# HendiRemoteInterface_v010.net
KiCad netlist of a schematic drawn in EAGLE
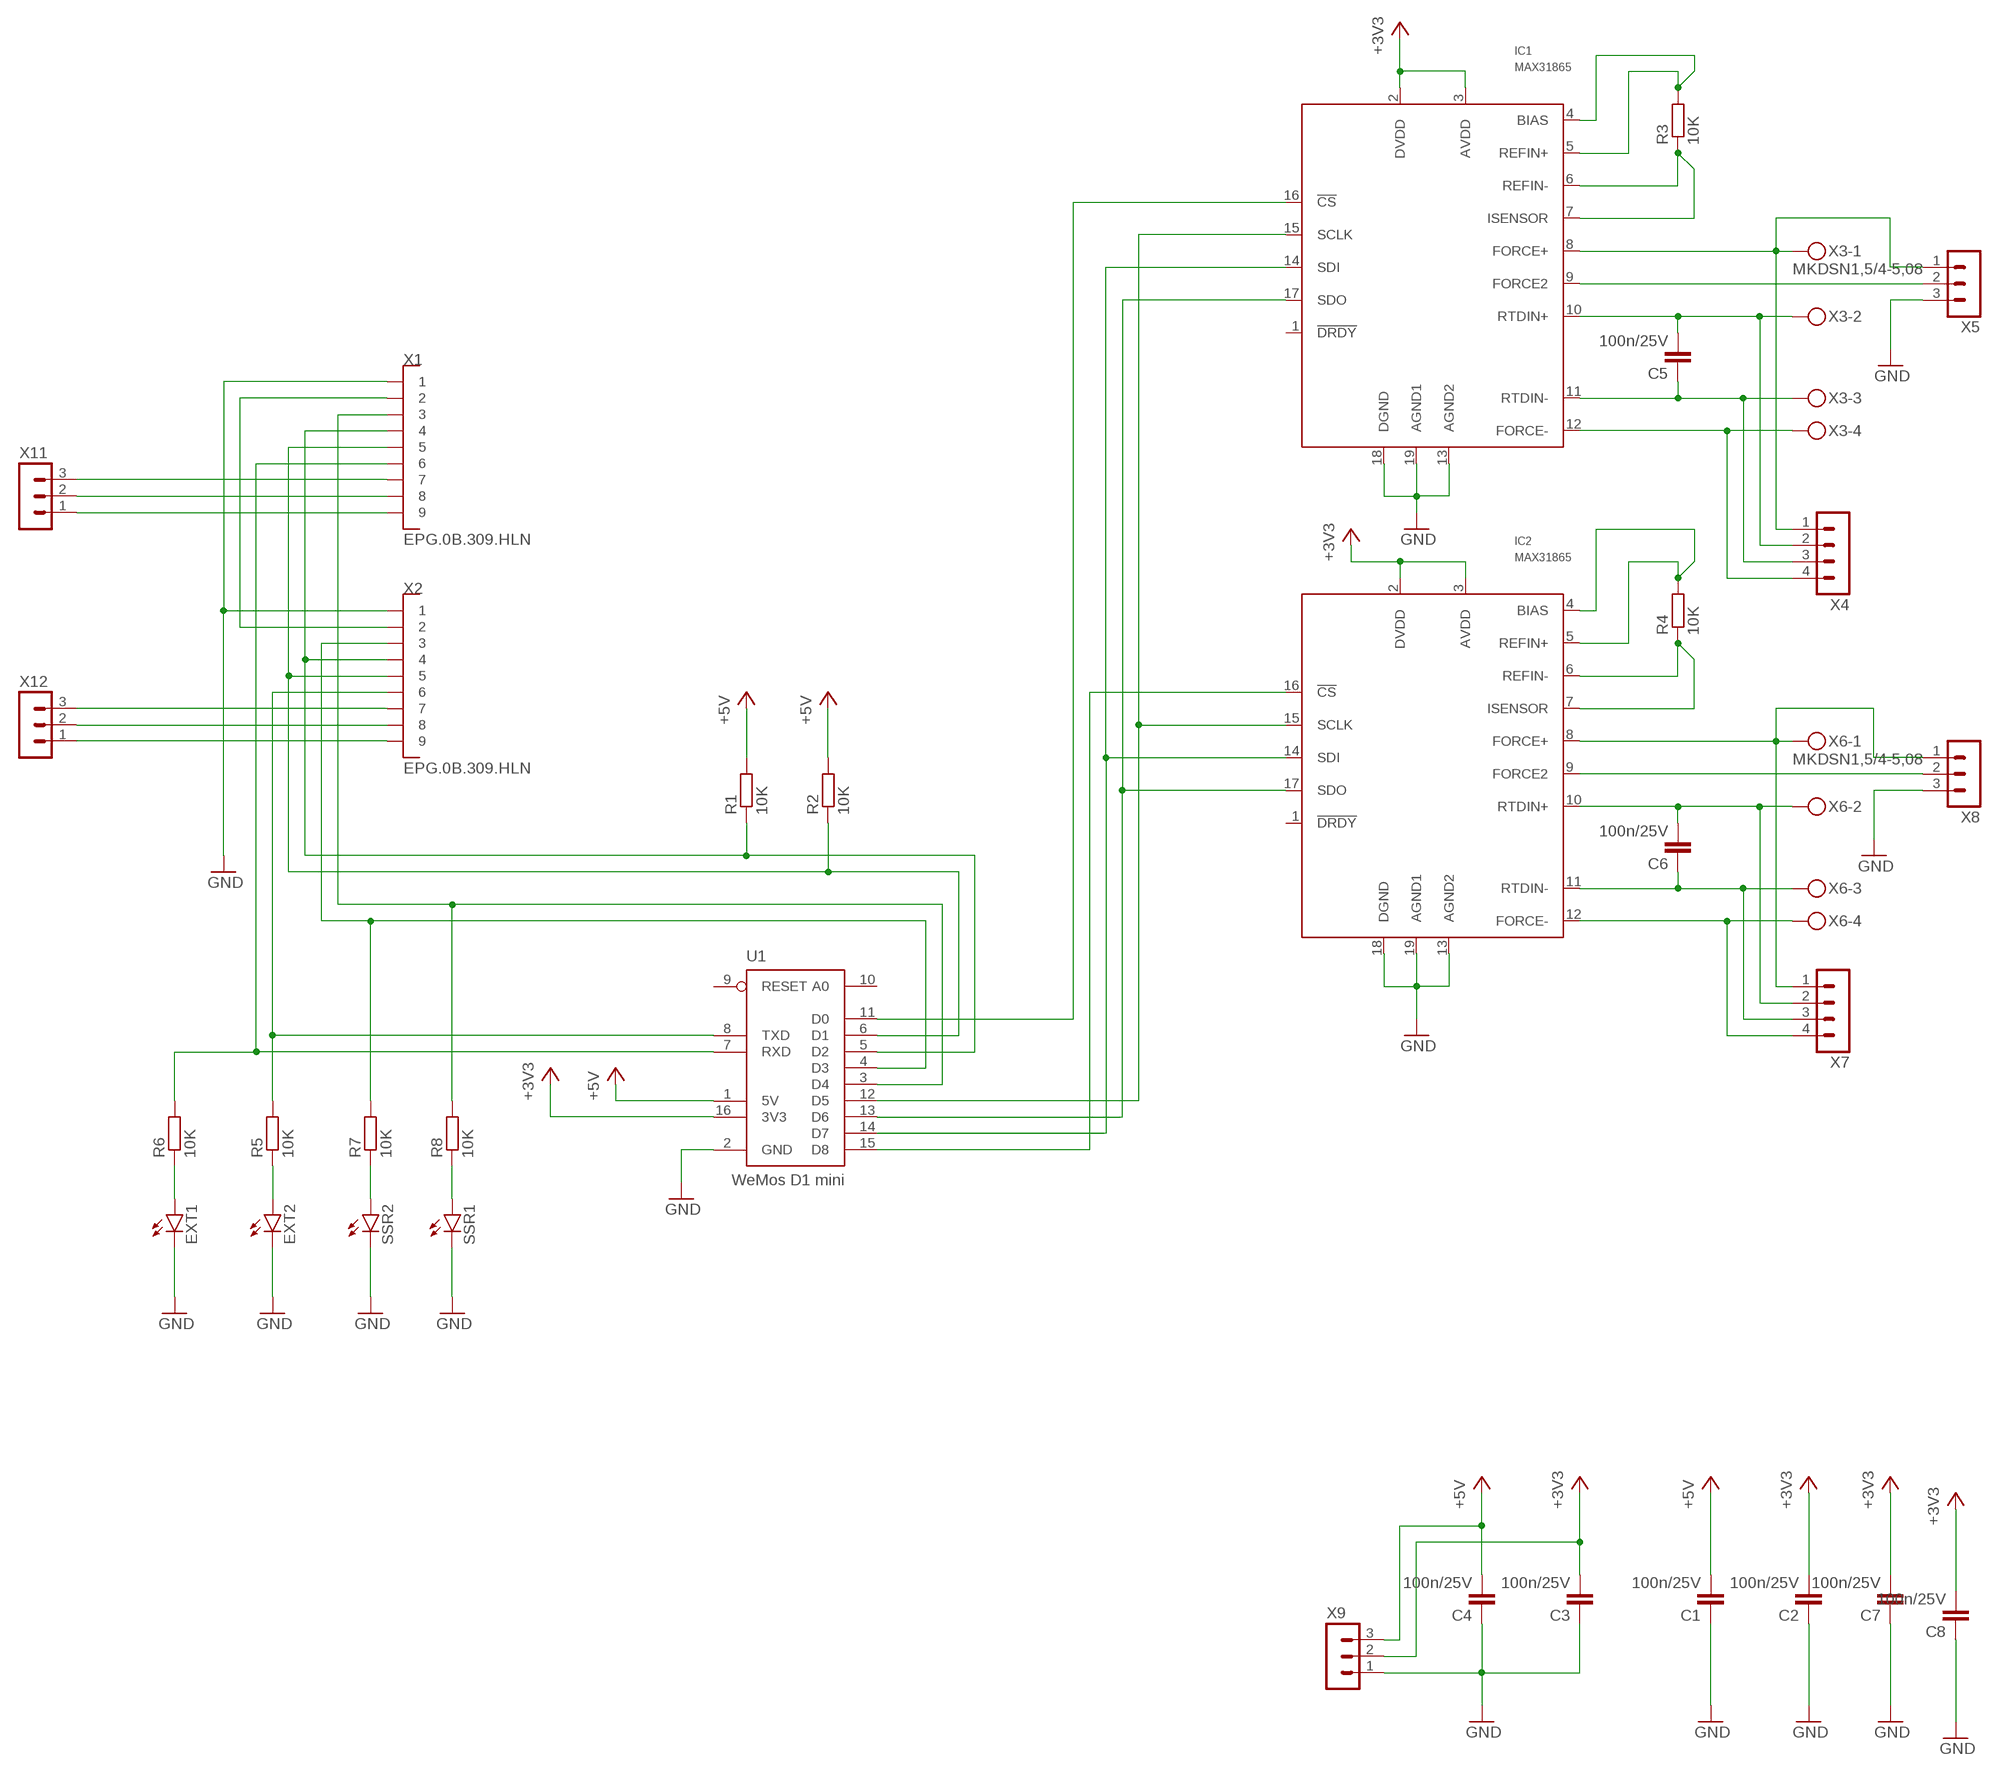
[diagram p0: schematic, sheet 1]

(export (version "E")
  (design (tool "Eeschema 10.0.6"))
  (components
    (comp (ref "C1")
      (value "100n/25V")
      (footprint "eagle-import:C0805")
      (libsource (lib "eagle-import") (part "C-EUC0805"))
    )
    (comp (ref "C2")
      (value "100n/25V")
      (footprint "eagle-import:C0805")
      (libsource (lib "eagle-import") (part "C-EUC0805"))
    )
    (comp (ref "C3")
      (value "100n/25V")
      (footprint "eagle-import:C0805")
      (libsource (lib "eagle-import") (part "C-EUC0805"))
    )
    (comp (ref "C4")
      (value "100n/25V")
      (footprint "eagle-import:C0805")
      (libsource (lib "eagle-import") (part "C-EUC0805"))
    )
    (comp (ref "C5")
      (value "100n/25V")
      (footprint "eagle-import:C0805")
      (libsource (lib "eagle-import") (part "C-EUC0805"))
    )
    (comp (ref "C6")
      (value "100n/25V")
      (footprint "eagle-import:C0805")
      (libsource (lib "eagle-import") (part "C-EUC0805"))
    )
    (comp (ref "C7")
      (value "100n/25V")
      (footprint "eagle-import:C0805")
      (libsource (lib "eagle-import") (part "C-EUC0805"))
    )
    (comp (ref "C8")
      (value "100n/25V")
      (footprint "eagle-import:C0805")
      (libsource (lib "eagle-import") (part "C-EUC0805"))
    )
    (comp (ref "EXT1")
      (value "LEDCHIP-LED0805")
      (footprint "eagle-import:CHIP-LED0805")
      (libsource (lib "eagle-import") (part "LEDCHIP-LED0805"))
    )
    (comp (ref "EXT2")
      (value "LEDCHIP-LED0805")
      (footprint "eagle-import:CHIP-LED0805")
      (libsource (lib "eagle-import") (part "LEDCHIP-LED0805"))
    )
    (comp (ref "IC1")
      (value "MAX31865")
      (footprint "eagle-import:SSOP20")
      (libsource (lib "eagle-import") (part "MAX31865-SSOPSSOP"))
    )
    (comp (ref "IC2")
      (value "MAX31865")
      (footprint "eagle-import:SSOP20")
      (libsource (lib "eagle-import") (part "MAX31865-SSOPSSOP"))
    )
    (comp (ref "R1")
      (value "10K")
      (footprint "eagle-import:R0805")
      (libsource (lib "eagle-import") (part "R-EU_R0805"))
    )
    (comp (ref "R2")
      (value "10K")
      (footprint "eagle-import:R0805")
      (libsource (lib "eagle-import") (part "R-EU_R0805"))
    )
    (comp (ref "R3")
      (value "10K")
      (footprint "eagle-import:R0805")
      (libsource (lib "eagle-import") (part "R-EU_R0805"))
    )
    (comp (ref "R4")
      (value "10K")
      (footprint "eagle-import:R0805")
      (libsource (lib "eagle-import") (part "R-EU_R0805"))
    )
    (comp (ref "R5")
      (value "10K")
      (footprint "eagle-import:R0805")
      (libsource (lib "eagle-import") (part "R-EU_R0805"))
    )
    (comp (ref "R6")
      (value "10K")
      (footprint "eagle-import:R0805")
      (libsource (lib "eagle-import") (part "R-EU_R0805"))
    )
    (comp (ref "R7")
      (value "10K")
      (footprint "eagle-import:R0805")
      (libsource (lib "eagle-import") (part "R-EU_R0805"))
    )
    (comp (ref "R8")
      (value "10K")
      (footprint "eagle-import:R0805")
      (libsource (lib "eagle-import") (part "R-EU_R0805"))
    )
    (comp (ref "SSR1")
      (value "LEDCHIP-LED0805")
      (footprint "eagle-import:CHIP-LED0805")
      (libsource (lib "eagle-import") (part "LEDCHIP-LED0805"))
    )
    (comp (ref "SSR2")
      (value "LEDCHIP-LED0805")
      (footprint "eagle-import:CHIP-LED0805")
      (libsource (lib "eagle-import") (part "LEDCHIP-LED0805"))
    )
    (comp (ref "U1")
      (value "WeMos D1 mini")
      (footprint "eagle-import:D1_MINI")
      (libsource (lib "eagle-import") (part "D1_MINI"))
    )
    (comp (ref "X1")
      (value "EPG.0B.309.HLN")
      (footprint "eagle-import:P19-EPG-EXG-0B.309")
      (libsource (lib "eagle-import") (part "EPG.0B.309.HLN"))
    )
    (comp (ref "X2")
      (value "EPG.0B.309.HLN")
      (footprint "eagle-import:P19-EPG-EXG-0B.309")
      (libsource (lib "eagle-import") (part "EPG.0B.309.HLN"))
    )
    (comp (ref "X3")
      (value "MKDSN1,5/4-5,08")
      (footprint "eagle-import:MKDSN1,5_4-5,08")
      (libsource (lib "eagle-import") (part "MKDSN1,5/4-5,08"))
    )
    (comp (ref "X4")
      (value "MA04-1")
      (footprint "eagle-import:MA04-1")
      (libsource (lib "eagle-import") (part "MA04-1"))
    )
    (comp (ref "X5")
      (value "MA03-1")
      (footprint "eagle-import:MA03-1")
      (libsource (lib "eagle-import") (part "MA03-1"))
    )
    (comp (ref "X6")
      (value "MKDSN1,5/4-5,08")
      (footprint "eagle-import:MKDSN1,5_4-5,08")
      (libsource (lib "eagle-import") (part "MKDSN1,5/4-5,08"))
    )
    (comp (ref "X7")
      (value "MA04-1")
      (footprint "eagle-import:MA04-1")
      (libsource (lib "eagle-import") (part "MA04-1"))
    )
    (comp (ref "X8")
      (value "MA03-1")
      (footprint "eagle-import:MA03-1")
      (libsource (lib "eagle-import") (part "MA03-1"))
    )
    (comp (ref "X9")
      (value "MA03-1")
      (footprint "eagle-import:MA03-1")
      (libsource (lib "eagle-import") (part "MA03-1"))
    )
    (comp (ref "X11")
      (value "MA03-1")
      (footprint "eagle-import:MA03-1")
      (libsource (lib "eagle-import") (part "MA03-1"))
    )
    (comp (ref "X12")
      (value "MA03-1")
      (footprint "eagle-import:MA03-1")
      (libsource (lib "eagle-import") (part "MA03-1"))
    )
  )
  (nets
    (net (code "1") (name "+3V3") (class "Default")
      (node (ref "C2") (pin "2") (pinfunction "2_2") (pintype "passive"))
      (node (ref "C3") (pin "2") (pinfunction "2_2") (pintype "passive"))
      (node (ref "C7") (pin "2") (pinfunction "2_2") (pintype "passive"))
      (node (ref "C8") (pin "2") (pinfunction "2_2") (pintype "passive"))
      (node (ref "IC1") (pin "2") (pinfunction "DVDD_2") (pintype "passive"))
      (node (ref "IC1") (pin "3") (pinfunction "AVDD_3") (pintype "passive"))
      (node (ref "IC2") (pin "2") (pinfunction "DVDD_2") (pintype "passive"))
      (node (ref "IC2") (pin "3") (pinfunction "AVDD_3") (pintype "passive"))
      (node (ref "U1") (pin "16") (pinfunction "3V3_16") (pintype "bidirectional"))
      (node (ref "X9") (pin "2") (pinfunction "2_2") (pintype "passive"))
    )
    (net (code "2") (name "+5V") (class "Default")
      (node (ref "C1") (pin "2") (pinfunction "2_2") (pintype "passive"))
      (node (ref "C4") (pin "2") (pinfunction "2_2") (pintype "passive"))
      (node (ref "R1") (pin "2") (pinfunction "2_2") (pintype "passive"))
      (node (ref "R2") (pin "2") (pinfunction "2_2") (pintype "passive"))
      (node (ref "U1") (pin "1") (pinfunction "5V_1") (pintype "bidirectional"))
      (node (ref "X9") (pin "3") (pinfunction "3_3") (pintype "passive"))
    )
    (net (code "3") (name "GND") (class "Default")
      (node (ref "C1") (pin "1") (pinfunction "1_1") (pintype "passive"))
      (node (ref "C2") (pin "1") (pinfunction "1_1") (pintype "passive"))
      (node (ref "C3") (pin "1") (pinfunction "1_1") (pintype "passive"))
      (node (ref "C4") (pin "1") (pinfunction "1_1") (pintype "passive"))
      (node (ref "C7") (pin "1") (pinfunction "1_1") (pintype "passive"))
      (node (ref "C8") (pin "1") (pinfunction "1_1") (pintype "passive"))
      (node (ref "EXT1") (pin "C") (pinfunction "C_C") (pintype "passive"))
      (node (ref "EXT2") (pin "C") (pinfunction "C_C") (pintype "passive"))
      (node (ref "IC1") (pin "13") (pinfunction "AGND2_13") (pintype "passive"))
      (node (ref "IC1") (pin "18") (pinfunction "DGND_18") (pintype "passive"))
      (node (ref "IC1") (pin "19") (pinfunction "AGND1_19") (pintype "passive"))
      (node (ref "IC2") (pin "13") (pinfunction "AGND2_13") (pintype "passive"))
      (node (ref "IC2") (pin "18") (pinfunction "DGND_18") (pintype "passive"))
      (node (ref "IC2") (pin "19") (pinfunction "AGND1_19") (pintype "passive"))
      (node (ref "SSR1") (pin "C") (pinfunction "C_C") (pintype "passive"))
      (node (ref "SSR2") (pin "C") (pinfunction "C_C") (pintype "passive"))
      (node (ref "U1") (pin "2") (pinfunction "GND_2") (pintype "bidirectional"))
      (node (ref "X1") (pin "1") (pinfunction "1_1") (pintype "bidirectional"))
      (node (ref "X2") (pin "1") (pinfunction "1_1") (pintype "bidirectional"))
      (node (ref "X5") (pin "3") (pinfunction "3_3") (pintype "passive"))
      (node (ref "X8") (pin "3") (pinfunction "3_3") (pintype "passive"))
      (node (ref "X9") (pin "1") (pinfunction "1_1") (pintype "passive"))
    )
    (net (code "4") (name "Net-(EXT1-PadA)") (class "Default")
      (node (ref "EXT1") (pin "A") (pinfunction "A_A") (pintype "passive"))
      (node (ref "R6") (pin "1") (pinfunction "1_1") (pintype "passive"))
    )
    (net (code "5") (name "Net-(EXT2-PadA)") (class "Default")
      (node (ref "EXT2") (pin "A") (pinfunction "A_A") (pintype "passive"))
      (node (ref "R5") (pin "1") (pinfunction "1_1") (pintype "passive"))
    )
    (net (code "6") (name "Net-(IC1-BIAS)") (class "Default")
      (node (ref "IC1") (pin "4") (pinfunction "BIAS_4") (pintype "passive"))
      (node (ref "IC1") (pin "5") (pinfunction "REFIN+_5") (pintype "passive"))
      (node (ref "R3") (pin "2") (pinfunction "2_2") (pintype "passive"))
    )
    (net (code "7") (name "Net-(IC1-FORCE+)") (class "Default")
      (node (ref "IC1") (pin "8") (pinfunction "FORCE+_8") (pintype "passive"))
      (node (ref "X3") (pin "1") (pinfunction "KL_1") (pintype "passive"))
      (node (ref "X4") (pin "1") (pinfunction "1_1") (pintype "passive"))
      (node (ref "X5") (pin "1") (pinfunction "1_1") (pintype "passive"))
    )
    (net (code "8") (name "Net-(IC1-FORCE-)") (class "Default")
      (node (ref "IC1") (pin "12") (pinfunction "FORCE-_12") (pintype "passive"))
      (node (ref "X3") (pin "4") (pinfunction "KL_4") (pintype "passive"))
      (node (ref "X4") (pin "4") (pinfunction "4_4") (pintype "passive"))
    )
    (net (code "9") (name "Net-(IC1-FORCE2)") (class "Default")
      (node (ref "IC1") (pin "9") (pinfunction "FORCE2_9") (pintype "passive"))
      (node (ref "X5") (pin "2") (pinfunction "2_2") (pintype "passive"))
    )
    (net (code "10") (name "Net-(IC1-ISENSOR)") (class "Default")
      (node (ref "IC1") (pin "6") (pinfunction "REFIN-_6") (pintype "passive"))
      (node (ref "IC1") (pin "7") (pinfunction "ISENSOR_7") (pintype "passive"))
      (node (ref "R3") (pin "1") (pinfunction "1_1") (pintype "passive"))
    )
    (net (code "11") (name "Net-(IC1-RTDIN+)") (class "Default")
      (node (ref "C5") (pin "2") (pinfunction "2_2") (pintype "passive"))
      (node (ref "IC1") (pin "10") (pinfunction "RTDIN+_10") (pintype "passive"))
      (node (ref "X3") (pin "2") (pinfunction "KL_2") (pintype "passive"))
      (node (ref "X4") (pin "2") (pinfunction "2_2") (pintype "passive"))
    )
    (net (code "12") (name "Net-(IC1-RTDIN-)") (class "Default")
      (node (ref "C5") (pin "1") (pinfunction "1_1") (pintype "passive"))
      (node (ref "IC1") (pin "11") (pinfunction "RTDIN-_11") (pintype "passive"))
      (node (ref "X3") (pin "3") (pinfunction "KL_3") (pintype "passive"))
      (node (ref "X4") (pin "3") (pinfunction "3_3") (pintype "passive"))
    )
    (net (code "13") (name "Net-(IC1-SCLK)") (class "Default")
      (node (ref "IC1") (pin "15") (pinfunction "SCLK_15") (pintype "passive"))
      (node (ref "IC2") (pin "15") (pinfunction "SCLK_15") (pintype "passive"))
      (node (ref "U1") (pin "12") (pinfunction "D5_12") (pintype "bidirectional"))
    )
    (net (code "14") (name "Net-(IC1-SDI)") (class "Default")
      (node (ref "IC1") (pin "14") (pinfunction "SDI_14") (pintype "passive"))
      (node (ref "IC2") (pin "14") (pinfunction "SDI_14") (pintype "passive"))
      (node (ref "U1") (pin "14") (pinfunction "D7_14") (pintype "bidirectional"))
    )
    (net (code "15") (name "Net-(IC1-SDO)") (class "Default")
      (node (ref "IC1") (pin "17") (pinfunction "SDO_17") (pintype "passive"))
      (node (ref "IC2") (pin "17") (pinfunction "SDO_17") (pintype "passive"))
      (node (ref "U1") (pin "13") (pinfunction "D6_13") (pintype "bidirectional"))
    )
    (net (code "16") (name "Net-(IC1-~{CS})") (class "Default")
      (node (ref "IC1") (pin "16") (pinfunction "~{CS}_16") (pintype "passive"))
      (node (ref "U1") (pin "11") (pinfunction "D0_11") (pintype "bidirectional"))
    )
    (net (code "17") (name "Net-(IC2-BIAS)") (class "Default")
      (node (ref "IC2") (pin "4") (pinfunction "BIAS_4") (pintype "passive"))
      (node (ref "IC2") (pin "5") (pinfunction "REFIN+_5") (pintype "passive"))
      (node (ref "R4") (pin "2") (pinfunction "2_2") (pintype "passive"))
    )
    (net (code "18") (name "Net-(IC2-FORCE+)") (class "Default")
      (node (ref "IC2") (pin "8") (pinfunction "FORCE+_8") (pintype "passive"))
      (node (ref "X6") (pin "1") (pinfunction "KL_1") (pintype "passive"))
      (node (ref "X7") (pin "1") (pinfunction "1_1") (pintype "passive"))
      (node (ref "X8") (pin "1") (pinfunction "1_1") (pintype "passive"))
    )
    (net (code "19") (name "Net-(IC2-FORCE-)") (class "Default")
      (node (ref "IC2") (pin "12") (pinfunction "FORCE-_12") (pintype "passive"))
      (node (ref "X6") (pin "4") (pinfunction "KL_4") (pintype "passive"))
      (node (ref "X7") (pin "4") (pinfunction "4_4") (pintype "passive"))
    )
    (net (code "20") (name "Net-(IC2-FORCE2)") (class "Default")
      (node (ref "IC2") (pin "9") (pinfunction "FORCE2_9") (pintype "passive"))
      (node (ref "X8") (pin "2") (pinfunction "2_2") (pintype "passive"))
    )
    (net (code "21") (name "Net-(IC2-ISENSOR)") (class "Default")
      (node (ref "IC2") (pin "6") (pinfunction "REFIN-_6") (pintype "passive"))
      (node (ref "IC2") (pin "7") (pinfunction "ISENSOR_7") (pintype "passive"))
      (node (ref "R4") (pin "1") (pinfunction "1_1") (pintype "passive"))
    )
    (net (code "22") (name "Net-(IC2-RTDIN+)") (class "Default")
      (node (ref "C6") (pin "2") (pinfunction "2_2") (pintype "passive"))
      (node (ref "IC2") (pin "10") (pinfunction "RTDIN+_10") (pintype "passive"))
      (node (ref "X6") (pin "2") (pinfunction "KL_2") (pintype "passive"))
      (node (ref "X7") (pin "2") (pinfunction "2_2") (pintype "passive"))
    )
    (net (code "23") (name "Net-(IC2-RTDIN-)") (class "Default")
      (node (ref "C6") (pin "1") (pinfunction "1_1") (pintype "passive"))
      (node (ref "IC2") (pin "11") (pinfunction "RTDIN-_11") (pintype "passive"))
      (node (ref "X6") (pin "3") (pinfunction "KL_3") (pintype "passive"))
      (node (ref "X7") (pin "3") (pinfunction "3_3") (pintype "passive"))
    )
    (net (code "24") (name "Net-(IC2-~{CS})") (class "Default")
      (node (ref "IC2") (pin "16") (pinfunction "~{CS}_16") (pintype "passive"))
      (node (ref "U1") (pin "15") (pinfunction "D8_15") (pintype "bidirectional"))
    )
    (net (code "25") (name "Net-(R7-Pad1)") (class "Default")
      (node (ref "R7") (pin "1") (pinfunction "1_1") (pintype "passive"))
      (node (ref "SSR2") (pin "A") (pinfunction "A_A") (pintype "passive"))
    )
    (net (code "26") (name "Net-(R8-Pad1)") (class "Default")
      (node (ref "R8") (pin "1") (pinfunction "1_1") (pintype "passive"))
      (node (ref "SSR1") (pin "A") (pinfunction "A_A") (pintype "passive"))
    )
    (net (code "27") (name "Net-(U1-D1)") (class "Default")
      (node (ref "R2") (pin "1") (pinfunction "1_1") (pintype "passive"))
      (node (ref "U1") (pin "6") (pinfunction "D1_6") (pintype "bidirectional"))
      (node (ref "X1") (pin "5") (pinfunction "5_5") (pintype "bidirectional"))
      (node (ref "X2") (pin "5") (pinfunction "5_5") (pintype "bidirectional"))
    )
    (net (code "28") (name "Net-(U1-D2)") (class "Default")
      (node (ref "R1") (pin "1") (pinfunction "1_1") (pintype "passive"))
      (node (ref "U1") (pin "5") (pinfunction "D2_5") (pintype "bidirectional"))
      (node (ref "X1") (pin "4") (pinfunction "4_4") (pintype "bidirectional"))
      (node (ref "X2") (pin "4") (pinfunction "4_4") (pintype "bidirectional"))
    )
    (net (code "29") (name "Net-(U1-D3)") (class "Default")
      (node (ref "R7") (pin "2") (pinfunction "2_2") (pintype "passive"))
      (node (ref "U1") (pin "4") (pinfunction "D3_4") (pintype "bidirectional"))
      (node (ref "X2") (pin "3") (pinfunction "3_3") (pintype "bidirectional"))
    )
    (net (code "30") (name "Net-(U1-D4)") (class "Default")
      (node (ref "R8") (pin "2") (pinfunction "2_2") (pintype "passive"))
      (node (ref "U1") (pin "3") (pinfunction "D4_3") (pintype "bidirectional"))
      (node (ref "X1") (pin "3") (pinfunction "3_3") (pintype "bidirectional"))
    )
    (net (code "31") (name "Net-(U1-RXD)") (class "Default")
      (node (ref "R6") (pin "2") (pinfunction "2_2") (pintype "passive"))
      (node (ref "U1") (pin "7") (pinfunction "RXD_7") (pintype "bidirectional"))
      (node (ref "X1") (pin "6") (pinfunction "6_6") (pintype "bidirectional"))
    )
    (net (code "32") (name "Net-(U1-TXD)") (class "Default")
      (node (ref "R5") (pin "2") (pinfunction "2_2") (pintype "passive"))
      (node (ref "U1") (pin "8") (pinfunction "TXD_8") (pintype "bidirectional"))
      (node (ref "X2") (pin "6") (pinfunction "6_6") (pintype "bidirectional"))
    )
    (net (code "33") (name "Net-(X1-Pad2)") (class "Default")
      (node (ref "X1") (pin "2") (pinfunction "2_2") (pintype "bidirectional"))
      (node (ref "X2") (pin "2") (pinfunction "2_2") (pintype "bidirectional"))
    )
    (net (code "34") (name "Net-(X1-Pad7)") (class "Default")
      (node (ref "X1") (pin "7") (pinfunction "7_7") (pintype "bidirectional"))
      (node (ref "X11") (pin "3") (pinfunction "3_3") (pintype "passive"))
    )
    (net (code "35") (name "Net-(X1-Pad8)") (class "Default")
      (node (ref "X1") (pin "8") (pinfunction "8_8") (pintype "bidirectional"))
      (node (ref "X11") (pin "2") (pinfunction "2_2") (pintype "passive"))
    )
    (net (code "36") (name "Net-(X1-Pad9)") (class "Default")
      (node (ref "X1") (pin "9") (pinfunction "9_9") (pintype "bidirectional"))
      (node (ref "X11") (pin "1") (pinfunction "1_1") (pintype "passive"))
    )
    (net (code "37") (name "Net-(X12-Pad1)") (class "Default")
      (node (ref "X12") (pin "1") (pinfunction "1_1") (pintype "passive"))
      (node (ref "X2") (pin "9") (pinfunction "9_9") (pintype "bidirectional"))
    )
    (net (code "38") (name "Net-(X12-Pad2)") (class "Default")
      (node (ref "X12") (pin "2") (pinfunction "2_2") (pintype "passive"))
      (node (ref "X2") (pin "8") (pinfunction "8_8") (pintype "bidirectional"))
    )
    (net (code "39") (name "Net-(X12-Pad3)") (class "Default")
      (node (ref "X12") (pin "3") (pinfunction "3_3") (pintype "passive"))
      (node (ref "X2") (pin "7") (pinfunction "7_7") (pintype "bidirectional"))
    )
    (net (code "40") (name "unconnected-(IC1-~{DRDY}-Pad1)") (class "Default")
      (node (ref "IC1") (pin "1") (pinfunction "~{DRDY}_1") (pintype "passive"))
    )
    (net (code "41") (name "unconnected-(IC2-~{DRDY}-Pad1)") (class "Default")
      (node (ref "IC2") (pin "1") (pinfunction "~{DRDY}_1") (pintype "passive"))
    )
    (net (code "42") (name "unconnected-(U1-A0-Pad10)") (class "Default")
      (node (ref "U1") (pin "10") (pinfunction "A0_10") (pintype "bidirectional"))
    )
    (net (code "43") (name "unconnected-(U1-RESET-Pad9)") (class "Default")
      (node (ref "U1") (pin "9") (pinfunction "RESET_9") (pintype "bidirectional"))
    )
  )
)
